# Radio.net
KiCad netlist of a schematic drawn in Altium Designer
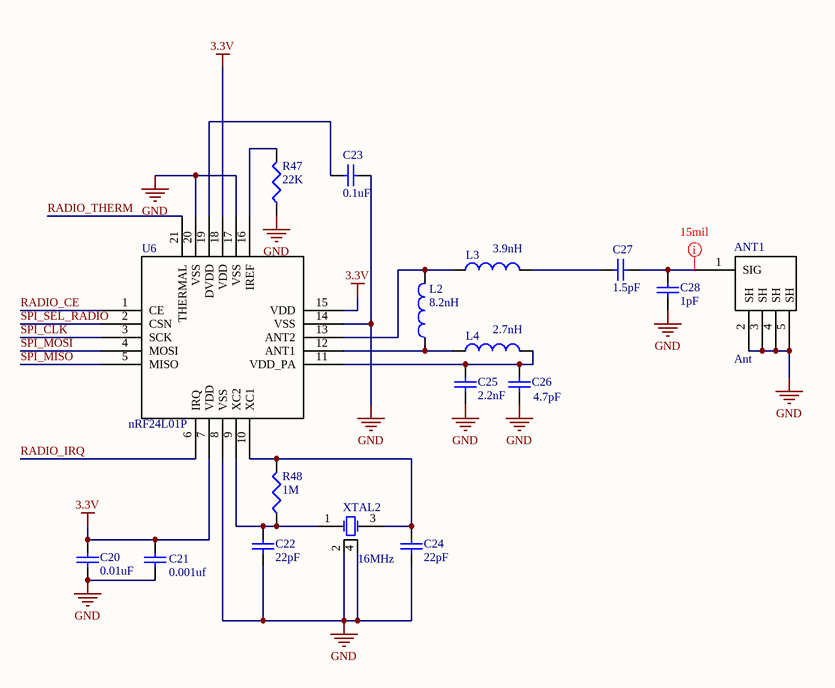
[diagram p0: Radio.SchDoc]

(export (version "E")
  (design (tool "Eeschema 10.0.6"))
  (components
    (comp (ref "ANT1") (value "Ant") (footprint "AntennaSMA") (libsource (lib "mrone") (part "AntennaConn")))
    (comp (ref "C20")
      (value "0.01uF")
      (footprint "CAPC1005L")
      (description "Capacitor (Semiconductor SIM Model)")
      (fields (field (name "Comment") "Cap Semi") (field (name "PUBLISHER") "Altium Limited"))
      (libsource (lib "Miscellaneous Devices") (part "Cap Semi"))
    )
    (comp (ref "C21")
      (value "0.001uf")
      (footprint "CAPC1005L")
      (description "Capacitor (Semiconductor SIM Model)")
      (fields (field (name "Comment") "Cap Semi") (field (name "PUBLISHER") "Altium Limited"))
      (libsource (lib "Miscellaneous Devices") (part "Cap Semi"))
    )
    (comp (ref "C22")
      (value "22pF")
      (footprint "CAPC1005L")
      (description "Capacitor (Semiconductor SIM Model)")
      (fields (field (name "Comment") "Cap Semi") (field (name "PUBLISHER") "Altium Limited"))
      (libsource (lib "Miscellaneous Devices") (part "Cap Semi"))
    )
    (comp (ref "C23")
      (value "0.1uF")
      (footprint "CAPC1005L")
      (description "Capacitor (Semiconductor SIM Model)")
      (fields (field (name "Comment") "Cap Semi") (field (name "PUBLISHER") "Altium Limited"))
      (libsource (lib "Miscellaneous Devices") (part "Cap Semi"))
    )
    (comp (ref "C24")
      (value "22pF")
      (footprint "CAPC1005L")
      (description "Capacitor (Semiconductor SIM Model)")
      (fields (field (name "Comment") "Cap Semi") (field (name "PUBLISHER") "Altium Limited"))
      (libsource (lib "Miscellaneous Devices") (part "Cap Semi"))
    )
    (comp (ref "C25")
      (value "2.2nF")
      (footprint "CAPC1005L")
      (description "Capacitor (Semiconductor SIM Model)")
      (fields (field (name "Comment") "Cap Semi") (field (name "PUBLISHER") "Altium Limited"))
      (libsource (lib "Miscellaneous Devices") (part "Cap Semi"))
    )
    (comp (ref "C26")
      (value "4.7pF")
      (footprint "CAPC1005L")
      (description "Capacitor (Semiconductor SIM Model)")
      (fields (field (name "Comment") "Cap Semi") (field (name "PUBLISHER") "Altium Limited"))
      (libsource (lib "Miscellaneous Devices") (part "Cap Semi"))
    )
    (comp (ref "C27")
      (value "1.5pF")
      (footprint "CAPC1005L")
      (description "Capacitor (Semiconductor SIM Model)")
      (fields (field (name "Comment") "Cap Semi") (field (name "PUBLISHER") "Altium Limited"))
      (libsource (lib "Miscellaneous Devices") (part "Cap Semi"))
    )
    (comp (ref "C28")
      (value "1pF")
      (footprint "CAPC1005L")
      (description "Capacitor (Semiconductor SIM Model)")
      (fields (field (name "Comment") "Cap Semi") (field (name "PUBLISHER") "Altium Limited"))
      (libsource (lib "Miscellaneous Devices") (part "Cap Semi"))
    )
    (comp (ref "L2")
      (value "8.2nH")
      (footprint "INDC1005AL")
      (description "Inductor")
      (fields (field (name "PUBLISHER") "Altium Limited"))
      (libsource (lib "Miscellaneous Devices") (part "Inductor"))
    )
    (comp (ref "L3")
      (value "3.9nH")
      (footprint "INDC1005AL")
      (description "Inductor")
      (fields (field (name "PUBLISHER") "Altium Limited"))
      (libsource (lib "Miscellaneous Devices") (part "Inductor"))
    )
    (comp (ref "L4")
      (value "2.7nH")
      (footprint "INDC1005AL")
      (description "Inductor")
      (fields (field (name "PUBLISHER") "Altium Limited"))
      (libsource (lib "Miscellaneous Devices") (part "Inductor"))
    )
    (comp (ref "R47")
      (value "22K")
      (footprint "RESC1608L")
      (description "Resistor")
      (fields (field (name "Comment") "Res3") (field (name "PUBLISHER") "Altium Limited"))
      (libsource (lib "Miscellaneous Devices") (part "Res3"))
    )
    (comp (ref "R48")
      (value "1M")
      (footprint "RESC1608L")
      (description "Resistor")
      (fields (field (name "Comment") "Res3") (field (name "PUBLISHER") "Altium Limited"))
      (libsource (lib "Miscellaneous Devices") (part "Res3"))
    )
    (comp (ref "U6")
      (value "nRF24L01P")
      (footprint "QFN-20")
      (libsource (lib "mrone") (part "radio-nRF24L01P"))
    )
    (comp (ref "XTAL2") (value "16MHz") (footprint "CRYSTAL") (libsource (lib "mrone") (part "Crystal")))
  )
  (nets
    (net (code "1") (name "/RADIO_CE") (class "Default")
      (node (ref "U6") (pin "1") (pinfunction "CE_1") (pintype "passive"))
    )
    (net (code "2") (name "/RADIO_IRQ") (class "Default")
      (node (ref "U6") (pin "6") (pinfunction "IRQ_6") (pintype "passive"))
    )
    (net (code "3") (name "/RADIO_THERM") (class "Default")
      (node (ref "U6") (pin "21") (pinfunction "THERMAL_21") (pintype "passive"))
    )
    (net (code "4") (name "/SPI_CLK") (class "Default")
      (node (ref "U6") (pin "3") (pinfunction "SCK_3") (pintype "passive"))
    )
    (net (code "5") (name "/SPI_MISO") (class "Default")
      (node (ref "U6") (pin "5") (pinfunction "MISO_5") (pintype "passive"))
    )
    (net (code "6") (name "/SPI_MOSI") (class "Default")
      (node (ref "U6") (pin "4") (pinfunction "MOSI_4") (pintype "passive"))
    )
    (net (code "7") (name "/SPI_SEL_RADIO") (class "Default")
      (node (ref "U6") (pin "2") (pinfunction "CSN_2") (pintype "passive"))
    )
    (net (code "8") (name "3.3V") (class "Default")
      (node (ref "C20") (pin "2") (pinfunction "2_2") (pintype "passive"))
      (node (ref "C21") (pin "2") (pinfunction "2_2") (pintype "passive"))
      (node (ref "U6") (pin "15") (pinfunction "VDD_15") (pintype "passive"))
      (node (ref "U6") (pin "18") (pinfunction "VDD_18") (pintype "passive"))
      (node (ref "U6") (pin "7") (pinfunction "VDD_7") (pintype "passive"))
    )
    (net (code "9") (name "GND") (class "Default")
      (node (ref "ANT1") (pin "2") (pinfunction "SH_2") (pintype "passive"))
      (node (ref "ANT1") (pin "3") (pinfunction "SH_3") (pintype "passive"))
      (node (ref "ANT1") (pin "4") (pinfunction "SH_4") (pintype "passive"))
      (node (ref "ANT1") (pin "5") (pinfunction "SH_5") (pintype "passive"))
      (node (ref "C20") (pin "1") (pinfunction "1_1") (pintype "passive"))
      (node (ref "C21") (pin "1") (pinfunction "1_1") (pintype "passive"))
      (node (ref "C22") (pin "1") (pinfunction "1_1") (pintype "passive"))
      (node (ref "C23") (pin "1") (pinfunction "1_1") (pintype "passive"))
      (node (ref "C24") (pin "1") (pinfunction "1_1") (pintype "passive"))
      (node (ref "C25") (pin "1") (pinfunction "1_1") (pintype "passive"))
      (node (ref "C26") (pin "1") (pinfunction "1_1") (pintype "passive"))
      (node (ref "C28") (pin "1") (pinfunction "1_1") (pintype "passive"))
      (node (ref "R47") (pin "1") (pinfunction "1_1") (pintype "passive"))
      (node (ref "U6") (pin "14") (pinfunction "VSS_14") (pintype "passive"))
      (node (ref "U6") (pin "17") (pinfunction "VSS_17") (pintype "passive"))
      (node (ref "U6") (pin "20") (pinfunction "VSS_20") (pintype "passive"))
      (node (ref "U6") (pin "8") (pinfunction "VSS_8") (pintype "passive"))
      (node (ref "XTAL2") (pin "2") (pinfunction "GND_2") (pintype "passive"))
      (node (ref "XTAL2") (pin "4") (pinfunction "GND_4") (pintype "passive"))
    )
    (net (code "10") (name "Net-(ANT1-SIG)") (class "Default")
      (node (ref "ANT1") (pin "1") (pinfunction "SIG_1") (pintype "passive"))
      (node (ref "C27") (pin "1") (pinfunction "1_1") (pintype "passive"))
      (node (ref "C28") (pin "2") (pinfunction "2_2") (pintype "passive"))
    )
    (net (code "11") (name "Net-(C27-Pad2)") (class "Default")
      (node (ref "C27") (pin "2") (pinfunction "2_2") (pintype "passive"))
      (node (ref "L3") (pin "2") (pinfunction "2_2") (pintype "passive"))
    )
    (net (code "12") (name "Net-(U6-ANT1)") (class "Default")
      (node (ref "L2") (pin "1") (pinfunction "1_1") (pintype "passive"))
      (node (ref "L4") (pin "1") (pinfunction "1_1") (pintype "passive"))
      (node (ref "U6") (pin "12") (pinfunction "ANT1_12") (pintype "passive"))
    )
    (net (code "13") (name "Net-(U6-ANT2)") (class "Default")
      (node (ref "L2") (pin "2") (pinfunction "2_2") (pintype "passive"))
      (node (ref "L3") (pin "1") (pinfunction "1_1") (pintype "passive"))
      (node (ref "U6") (pin "13") (pinfunction "ANT2_13") (pintype "passive"))
    )
    (net (code "14") (name "Net-(U6-DVDD)") (class "Default")
      (node (ref "C23") (pin "2") (pinfunction "2_2") (pintype "passive"))
      (node (ref "U6") (pin "19") (pinfunction "DVDD_19") (pintype "passive"))
    )
    (net (code "15") (name "Net-(U6-IREF)") (class "Default")
      (node (ref "R47") (pin "2") (pinfunction "2_2") (pintype "passive"))
      (node (ref "U6") (pin "16") (pinfunction "IREF_16") (pintype "passive"))
    )
    (net (code "16") (name "Net-(U6-VDD_PA)") (class "Default")
      (node (ref "C25") (pin "2") (pinfunction "2_2") (pintype "passive"))
      (node (ref "C26") (pin "2") (pinfunction "2_2") (pintype "passive"))
      (node (ref "L4") (pin "2") (pinfunction "2_2") (pintype "passive"))
      (node (ref "U6") (pin "11") (pinfunction "VDD_PA_11") (pintype "passive"))
    )
    (net (code "17") (name "Net-(U6-XC1)") (class "Default")
      (node (ref "C24") (pin "2") (pinfunction "2_2") (pintype "passive"))
      (node (ref "R48") (pin "2") (pinfunction "2_2") (pintype "passive"))
      (node (ref "U6") (pin "10") (pinfunction "XC1_10") (pintype "passive"))
      (node (ref "XTAL2") (pin "3") (pinfunction "OSC2_3") (pintype "passive"))
    )
    (net (code "18") (name "Net-(U6-XC2)") (class "Default")
      (node (ref "C22") (pin "2") (pinfunction "2_2") (pintype "passive"))
      (node (ref "R48") (pin "1") (pinfunction "1_1") (pintype "passive"))
      (node (ref "U6") (pin "9") (pinfunction "XC2_9") (pintype "passive"))
      (node (ref "XTAL2") (pin "1") (pinfunction "OSC1_1") (pintype "passive"))
    )
  )
)
